# ArduinoRev2.net
KiCad netlist of a schematic drawn in Altium Designer
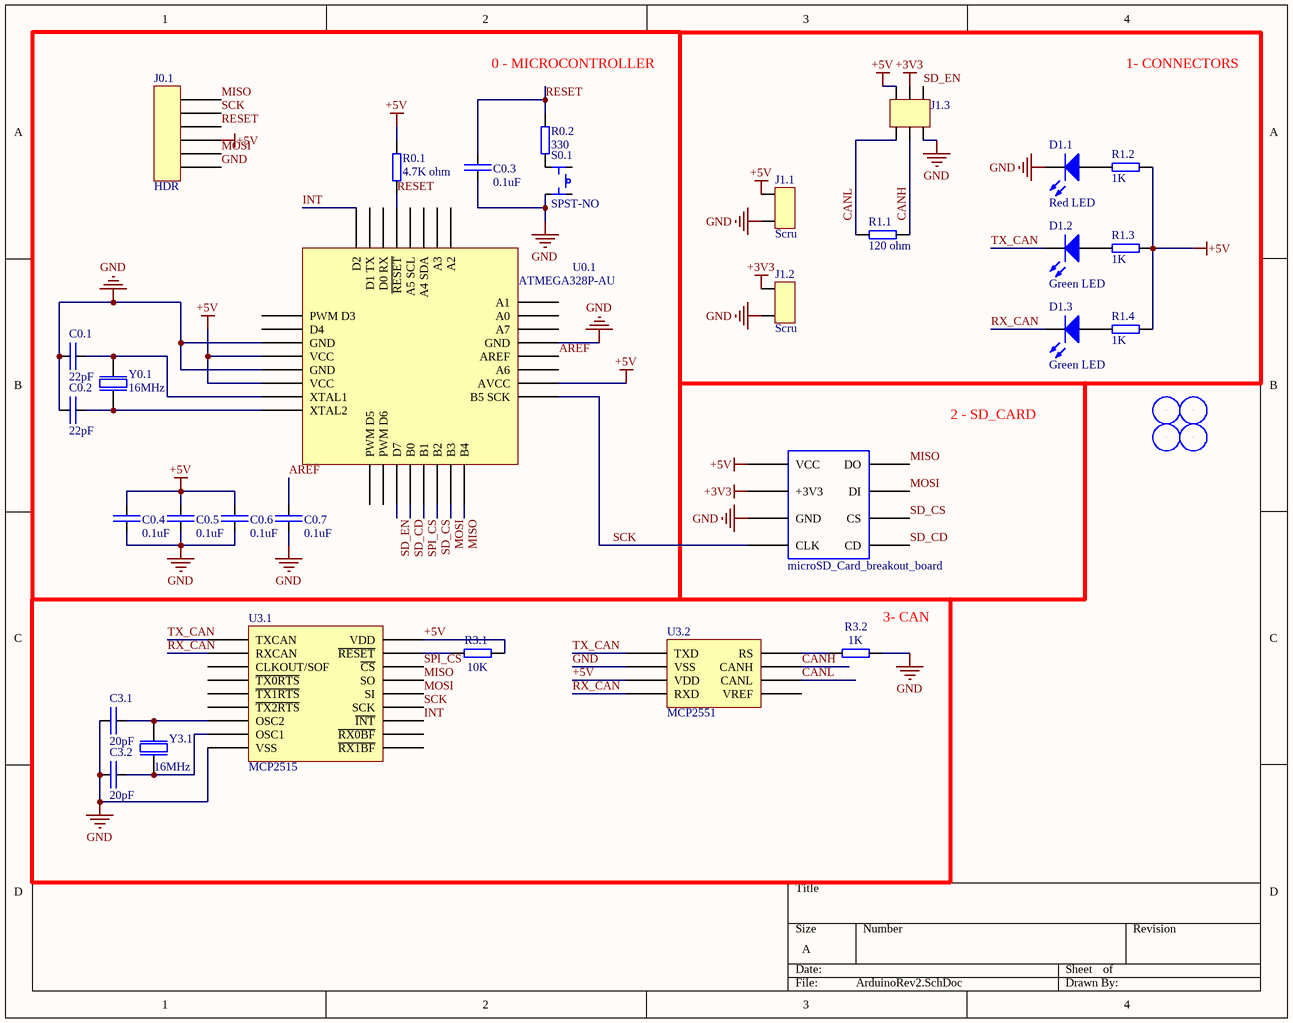
[diagram p0: ArduinoRev2.SchDoc]

(export (version "E")
  (design (tool "Eeschema 10.0.6"))
  (components
    (comp (ref "C0.1")
      (value "22pF")
      (footprint "C0805")
      (description "CAP CER 22PF 50V C0G/NPO 0805")
      (libsource (lib "Atmega328p") (part "CC0805JRNPO9BN220"))
    )
    (comp (ref "C0.2")
      (value "22pF")
      (footprint "C0805")
      (description "CAP CER 22PF 50V C0G/NPO 0805")
      (libsource (lib "Atmega328p") (part "CC0805JRNPO9BN220"))
    )
    (comp (ref "C0.3")
      (value "0.1uF")
      (footprint "C0805")
      (description "CAP CER 0.1UF 50V X7R 0805")
      (fields
        (field (name "MANUFACTURER") "Samsung")
        (field (name "MANUFACTURER PART NUMBER") "CL21B104KBCWPNC")
      )
      (libsource (lib "Capacitors") (part "CL21B104KBCWPNC"))
    )
    (comp (ref "C0.4")
      (value "0.1uF")
      (footprint "C0805")
      (description "CAP CER 0.1UF 50V X7R 0805")
      (fields
        (field (name "MANUFACTURER") "Samsung")
        (field (name "MANUFACTURER PART NUMBER") "CL21B104KBCWPNC")
      )
      (libsource (lib "Capacitors") (part "CL21B104KBCWPNC"))
    )
    (comp (ref "C0.5")
      (value "0.1uF")
      (footprint "C0805")
      (description "CAP CER 0.1UF 50V X7R 0805")
      (fields
        (field (name "MANUFACTURER") "Samsung")
        (field (name "MANUFACTURER PART NUMBER") "CL21B104KBCWPNC")
      )
      (libsource (lib "Capacitors") (part "CL21B104KBCWPNC"))
    )
    (comp (ref "C0.6")
      (value "0.1uF")
      (footprint "C0805")
      (description "CAP CER 0.1UF 50V X7R 0805")
      (fields
        (field (name "MANUFACTURER") "Samsung")
        (field (name "MANUFACTURER PART NUMBER") "CL21B104KBCWPNC")
      )
      (libsource (lib "Capacitors") (part "CL21B104KBCWPNC"))
    )
    (comp (ref "C0.7")
      (value "0.1uF")
      (footprint "C0805")
      (description "CAP CER 0.1UF 50V X7R 0805")
      (fields
        (field (name "MANUFACTURER") "Samsung")
        (field (name "MANUFACTURER PART NUMBER") "CL21B104KBCWPNC")
      )
      (libsource (lib "Capacitors") (part "CL21B104KBCWPNC"))
    )
    (comp (ref "C3.1")
      (value "20pF")
      (footprint "C0805")
      (description "CAP CER 20PF 50V C0G/NP0 0805")
      (fields
        (field (name "MANUFACTURER") "Samsung")
        (field (name "MANUFACTURER PART NUMBER") "CL21B103KBANNNC")
      )
      (libsource (lib "Capacitors") (part "C0805C200J5GACTU"))
    )
    (comp (ref "C3.2")
      (value "20pF")
      (footprint "C0805")
      (description "CAP CER 20PF 50V C0G/NP0 0805")
      (fields
        (field (name "MANUFACTURER") "Samsung")
        (field (name "MANUFACTURER PART NUMBER") "CL21B103KBANNNC")
      )
      (libsource (lib "Capacitors") (part "C0805C200J5GACTU"))
    )
    (comp (ref "D1.1")
      (value "Red LED")
      (footprint "L0805")
      (description "LED RED DIFFUSED 0805 SMD")
      (fields
        (field (name "MANUFACTURER") "Lumex")
        (field (name "MANUFACTURER PART NUMBER") "SML-LXT0805SRW-TR")
      )
      (libsource (lib "Indication & Control") (part "SML-LXT0805SRW-TR"))
    )
    (comp (ref "D1.2")
      (value "Green LED")
      (footprint "L0805")
      (description "LED GREEN DIFFUSED SMD")
      (fields
        (field (name "MANUFACTURER") "Lumex")
        (field (name "MANUFACTURER PART NUMBER") "SML-LXT0805GW-TR")
      )
      (libsource (lib "Indication & Control") (part "SML-LXT0805GW-TR"))
    )
    (comp (ref "D1.3")
      (value "Green LED")
      (footprint "L0805")
      (description "LED GREEN DIFFUSED SMD")
      (fields
        (field (name "MANUFACTURER") "Lumex")
        (field (name "MANUFACTURER PART NUMBER") "SML-LXT0805GW-TR")
      )
      (libsource (lib "Indication & Control") (part "SML-LXT0805GW-TR"))
    )
    (comp (ref "J0.1")
      (value "HDR")
      (footprint "961206-6404-AR")
      (description "CONN HEADER VERT 6POS 2.54MM")
      (libsource (lib "Atmega328p") (part "961206-6404-AR"))
    )
    (comp (ref "J1.1")
      (value "Scru")
      (footprint "5mm 2POS Screw terminal")
      (libsource (lib "Connectors") (part "5mm 2POS Screw terminal"))
    )
    (comp (ref "J1.2")
      (value "Scru")
      (footprint "5mm 2POS Screw terminal")
      (libsource (lib "Connectors") (part "5mm 2POS Screw terminal"))
    )
    (comp (ref "J1.3")
      (value "43045-0600")
      (footprint "Micro-Fit 3.0 6pos")
      (description "Micro-fit 3.0 6pos right-angle")
      (fields (field (name "MANUFACTURER") "Molex") (field (name "MANUFACTURER PART NUMBER") "43045-0612"))
      (libsource (lib "Connectors") (part "43045-0600"))
    )
    (comp (ref "M1")
      (value "3mm Mounting Hole")
      (footprint "3mm Mounting Hole")
      (libsource (lib "Misc Components") (part "3mm Mounting Hole"))
    )
    (comp (ref "M2")
      (value "3mm Mounting Hole")
      (footprint "3mm Mounting Hole")
      (libsource (lib "Misc Components") (part "3mm Mounting Hole"))
    )
    (comp (ref "M3")
      (value "3mm Mounting Hole")
      (footprint "3mm Mounting Hole")
      (libsource (lib "Misc Components") (part "3mm Mounting Hole"))
    )
    (comp (ref "M4")
      (value "3mm Mounting Hole")
      (footprint "3mm Mounting Hole")
      (libsource (lib "Misc Components") (part "3mm Mounting Hole"))
    )
    (comp (ref "R0.1")
      (value "4.7K ohm")
      (footprint "R0805")
      (description "RES SMD 4.7K OHM 5% 1/8W 0805")
      (libsource (lib "Atmega328p") (part "RC0805JR-074K7L"))
    )
    (comp (ref "R0.2")
      (value "330")
      (footprint "R0805")
      (description "RES SMD 330 OHM 5% 1/8W 0805")
      (libsource (lib "Atmega328p") (part "RC0805JR-074K7L_1"))
    )
    (comp (ref "R1.1")
      (value "120 ohm")
      (footprint "R0805")
      (description "RES SMD 120 OHM 1% 1/8W 0805")
      (libsource (lib "Resistors") (part "ERJ6ENV1200V"))
    )
    (comp (ref "R1.2")
      (value "1K")
      (footprint "R0805")
      (description "RES SMD 1K OHM 1% 1/8W 0805")
      (fields
        (field (name "MANUFACTURER") "Panasonic")
        (field (name "MANUFACTURER PART NUMBER") "ERJ6ENF1001V")
      )
      (libsource (lib "Resistors") (part "ERJ6ENF1001V"))
    )
    (comp (ref "R1.3")
      (value "1K")
      (footprint "R0805")
      (description "RES SMD 1K OHM 1% 1/8W 0805")
      (fields
        (field (name "MANUFACTURER") "Panasonic")
        (field (name "MANUFACTURER PART NUMBER") "ERJ6ENF1001V")
      )
      (libsource (lib "Resistors") (part "ERJ6ENF1001V"))
    )
    (comp (ref "R1.4")
      (value "1K")
      (footprint "R0805")
      (description "RES SMD 1K OHM 1% 1/8W 0805")
      (fields
        (field (name "MANUFACTURER") "Panasonic")
        (field (name "MANUFACTURER PART NUMBER") "ERJ6ENF1001V")
      )
      (libsource (lib "Resistors") (part "ERJ6ENF1001V"))
    )
    (comp (ref "R3.1")
      (value "10K")
      (footprint "R0805")
      (description "RES SMD 10K OHM 1% 1/8W 0805")
      (fields (field (name "MANUFACTURER") "Yageo") (field (name "MANUFACTURER PART NUMBER") "ERJ-6ENF1002V"))
      (libsource (lib "Resistors") (part "ERJ6ENF1002V"))
    )
    (comp (ref "R3.2")
      (value "1K")
      (footprint "R0805")
      (description "RES SMD 1K OHM 1% 1/8W 0805")
      (fields
        (field (name "MANUFACTURER") "Panasonic")
        (field (name "MANUFACTURER PART NUMBER") "ERJ6ENF1001V")
      )
      (libsource (lib "Resistors") (part "ERJ6ENF1001V"))
    )
    (comp (ref "S0.1")
      (value "SPST-NO")
      (footprint "PTS526 SM15 SMTR2 LFS")
      (description "TACT 5.2 X 5.2, 1.5 MM H, 160GF, Tactile Switch SPST-NO Top Actuated Surface Mount")
      (fields
        (field (name "MANUFACTURER") "ITT C&K")
        (field (name "MANUFACTURER PART NUMBER") "PTS526SM15SMTR2LFS")
      )
      (libsource (lib "Indication & Control") (part "PTS526SM15SMTR2LFS"))
    )
    (comp (ref "U0.1")
      (value "ATMEGA328P-AU")
      (footprint "TQFP80P900X900X120-32N")
      (fields (field (name "CREATED BY") "Joseph Park"))
      (libsource (lib "Atmega328p") (part "ATMEGA328P-AU"))
    )
    (comp (ref "U2.1")
      (value "microSD_Card_breakout_board")
      (footprint "Adafruit microSD_breakoutboard")
      (libsource (lib "Atmega328p") (part "microSD_Card_breakout_board"))
    )
    (comp (ref "U3.1")
      (value "MCP2515")
      (footprint "SOP18")
      (description "Stand-Alone CAN Controller with SPI Interface")
      (libsource (lib "Atmega328p") (part "MCP2515"))
    )
    (comp (ref "U3.2")
      (value "MCP2551")
      (footprint "SOP8")
      (description "High Speed Can Transceiver")
      (libsource (lib "Atmega328p") (part "MCP2551"))
    )
    (comp (ref "Y0.1")
      (value "16MHz")
      (footprint "ECS-160-20-3X-TR")
      (description "CRYSTAL 16.0000MHZ 20PF SMD")
      (libsource (lib "Atmega328p") (part "ECS-160-20-3X-TR"))
    )
    (comp (ref "Y3.1")
      (value "16MHz")
      (footprint "ECS-160-20-3X-TR")
      (description "CRYSTAL 16.0000MHZ 20PF SMD")
      (libsource (lib "Atmega328p") (part "ECS-160-20-3X-TR"))
    )
  )
  (nets
    (net (code "1") (name "+3V3") (class "Default")
      (node (ref "J1.2") (pin "1") (pinfunction "1_1") (pintype "passive"))
      (node (ref "J1.3") (pin "5") (pinfunction "5_5") (pintype "passive"))
      (node (ref "U2.1") (pin "2") (pinfunction "+3V3_2") (pintype "passive"))
    )
    (net (code "2") (name "+5V") (class "Default")
      (node (ref "C0.4") (pin "2") (pinfunction "2_2") (pintype "passive"))
      (node (ref "C0.5") (pin "2") (pinfunction "2_2") (pintype "passive"))
      (node (ref "C0.6") (pin "2") (pinfunction "2_2") (pintype "passive"))
      (node (ref "J0.1") (pin "4") (pinfunction "4_4") (pintype "passive"))
      (node (ref "J1.1") (pin "1") (pinfunction "1_1") (pintype "passive"))
      (node (ref "J1.3") (pin "6") (pinfunction "6_6") (pintype "passive"))
      (node (ref "R0.1") (pin "2") (pinfunction "2_2") (pintype "passive"))
      (node (ref "R1.2") (pin "2") (pinfunction "2_2") (pintype "passive"))
      (node (ref "R1.3") (pin "2") (pinfunction "2_2") (pintype "passive"))
      (node (ref "R1.4") (pin "2") (pinfunction "2_2") (pintype "passive"))
      (node (ref "R3.1") (pin "2") (pinfunction "2_2") (pintype "passive"))
      (node (ref "U0.1") (pin "18") (pinfunction "AVCC_18") (pintype "passive"))
      (node (ref "U0.1") (pin "4") (pinfunction "VCC_4") (pintype "passive"))
      (node (ref "U0.1") (pin "6") (pinfunction "VCC_6") (pintype "passive"))
      (node (ref "U2.1") (pin "1") (pinfunction "VCC_1") (pintype "passive"))
      (node (ref "U3.1") (pin "18") (pinfunction "VDD_18") (pintype "passive"))
      (node (ref "U3.2") (pin "3") (pinfunction "VDD_3") (pintype "passive"))
    )
    (net (code "3") (name "/AREF") (class "Default")
      (node (ref "C0.7") (pin "2") (pinfunction "2_2") (pintype "passive"))
      (node (ref "U0.1") (pin "20") (pinfunction "AREF_20") (pintype "passive"))
    )
    (net (code "4") (name "/CANH") (class "Default")
      (node (ref "J1.3") (pin "2") (pinfunction "2_2") (pintype "passive"))
      (node (ref "R1.1") (pin "2") (pinfunction "2_2") (pintype "passive"))
      (node (ref "U3.2") (pin "7") (pinfunction "CANH_7") (pintype "passive"))
    )
    (net (code "5") (name "/CANL") (class "Default")
      (node (ref "J1.3") (pin "3") (pinfunction "3_3") (pintype "passive"))
      (node (ref "R1.1") (pin "1") (pinfunction "1_1") (pintype "passive"))
      (node (ref "U3.2") (pin "6") (pinfunction "CANL_6") (pintype "passive"))
    )
    (net (code "6") (name "/INT") (class "Default")
      (node (ref "U0.1") (pin "32") (pinfunction "D2_32") (pintype "passive"))
      (node (ref "U3.1") (pin "12") (pinfunction "~{INT}_12") (pintype "passive"))
    )
    (net (code "7") (name "/MISO") (class "Default")
      (node (ref "J0.1") (pin "1") (pinfunction "1_1") (pintype "passive"))
      (node (ref "U0.1") (pin "16") (pinfunction "B4_16") (pintype "passive"))
      (node (ref "U2.1") (pin "5") (pinfunction "DO_5") (pintype "passive"))
      (node (ref "U3.1") (pin "15") (pinfunction "SO_15") (pintype "passive"))
    )
    (net (code "8") (name "/MOSI") (class "Default")
      (node (ref "J0.1") (pin "5") (pinfunction "5_5") (pintype "passive"))
      (node (ref "U0.1") (pin "15") (pinfunction "B3_15") (pintype "passive"))
      (node (ref "U2.1") (pin "6") (pinfunction "DI_6") (pintype "passive"))
      (node (ref "U3.1") (pin "14") (pinfunction "SI_14") (pintype "passive"))
    )
    (net (code "9") (name "/RESET") (class "Default")
      (node (ref "C0.3") (pin "2") (pinfunction "2_2") (pintype "passive"))
      (node (ref "J0.1") (pin "3") (pinfunction "3_3") (pintype "passive"))
      (node (ref "R0.1") (pin "1") (pinfunction "1_1") (pintype "passive"))
      (node (ref "R0.2") (pin "2") (pinfunction "2_2") (pintype "passive"))
      (node (ref "U0.1") (pin "29") (pinfunction "~{RESET}_29") (pintype "passive"))
    )
    (net (code "10") (name "/RX_CAN") (class "Default")
      (node (ref "D1.3") (pin "2") (pinfunction "K_2") (pintype "passive"))
      (node (ref "U3.1") (pin "2") (pinfunction "RXCAN_2") (pintype "passive"))
      (node (ref "U3.2") (pin "4") (pinfunction "RXD_4") (pintype "passive"))
    )
    (net (code "11") (name "/SCK") (class "Default")
      (node (ref "J0.1") (pin "2") (pinfunction "2_2") (pintype "passive"))
      (node (ref "U0.1") (pin "17") (pinfunction "B5_SCK_17") (pintype "passive"))
      (node (ref "U2.1") (pin "4") (pinfunction "CLK_4") (pintype "passive"))
      (node (ref "U3.1") (pin "13") (pinfunction "SCK_13") (pintype "passive"))
    )
    (net (code "12") (name "/SD_CD") (class "Default")
      (node (ref "U0.1") (pin "12") (pinfunction "B0_12") (pintype "passive"))
      (node (ref "U2.1") (pin "8") (pinfunction "CD_8") (pintype "passive"))
    )
    (net (code "13") (name "/SD_CS") (class "Default")
      (node (ref "U0.1") (pin "14") (pinfunction "B2_14") (pintype "passive"))
      (node (ref "U2.1") (pin "7") (pinfunction "CS_7") (pintype "passive"))
    )
    (net (code "14") (name "/SD_EN") (class "Default")
      (node (ref "J1.3") (pin "4") (pinfunction "4_4") (pintype "passive"))
      (node (ref "U0.1") (pin "11") (pinfunction "D7_11") (pintype "passive"))
    )
    (net (code "15") (name "/SPI_CS") (class "Default")
      (node (ref "U0.1") (pin "13") (pinfunction "B1_13") (pintype "passive"))
      (node (ref "U3.1") (pin "16") (pinfunction "~{CS}_16") (pintype "passive"))
    )
    (net (code "16") (name "/TX_CAN") (class "Default")
      (node (ref "D1.2") (pin "2") (pinfunction "K_2") (pintype "passive"))
      (node (ref "U3.1") (pin "1") (pinfunction "TXCAN_1") (pintype "passive"))
      (node (ref "U3.2") (pin "1") (pinfunction "TXD_1") (pintype "passive"))
    )
    (net (code "17") (name "GND") (class "Default")
      (node (ref "C0.1") (pin "1") (pinfunction "1_1") (pintype "passive"))
      (node (ref "C0.2") (pin "1") (pinfunction "1_1") (pintype "passive"))
      (node (ref "C0.3") (pin "1") (pinfunction "1_1") (pintype "passive"))
      (node (ref "C0.4") (pin "1") (pinfunction "1_1") (pintype "passive"))
      (node (ref "C0.5") (pin "1") (pinfunction "1_1") (pintype "passive"))
      (node (ref "C0.6") (pin "1") (pinfunction "1_1") (pintype "passive"))
      (node (ref "C0.7") (pin "1") (pinfunction "1_1") (pintype "passive"))
      (node (ref "C3.1") (pin "1") (pinfunction "1_1") (pintype "passive"))
      (node (ref "C3.2") (pin "1") (pinfunction "1_1") (pintype "passive"))
      (node (ref "D1.1") (pin "2") (pinfunction "K_2") (pintype "passive"))
      (node (ref "J0.1") (pin "6") (pinfunction "6_6") (pintype "passive"))
      (node (ref "J1.1") (pin "2") (pinfunction "2_2") (pintype "passive"))
      (node (ref "J1.2") (pin "2") (pinfunction "2_2") (pintype "passive"))
      (node (ref "J1.3") (pin "1") (pinfunction "1_1") (pintype "passive"))
      (node (ref "R3.2") (pin "2") (pinfunction "2_2") (pintype "passive"))
      (node (ref "S0.1") (pin "3") (pinfunction "NO_3") (pintype "passive"))
      (node (ref "U0.1") (pin "21") (pinfunction "GND_21") (pintype "passive"))
      (node (ref "U0.1") (pin "3") (pinfunction "GND_3") (pintype "passive"))
      (node (ref "U0.1") (pin "5") (pinfunction "GND_5") (pintype "passive"))
      (node (ref "U2.1") (pin "3") (pinfunction "GND_3") (pintype "passive"))
      (node (ref "U3.1") (pin "9") (pinfunction "VSS_9") (pintype "passive"))
      (node (ref "U3.2") (pin "2") (pinfunction "VSS_2") (pintype "passive"))
    )
    (net (code "18") (name "Net-(D1.1-A)") (class "Default")
      (node (ref "D1.1") (pin "1") (pinfunction "A_1") (pintype "passive"))
      (node (ref "R1.2") (pin "1") (pinfunction "1_1") (pintype "passive"))
    )
    (net (code "19") (name "Net-(D1.2-A)") (class "Default")
      (node (ref "D1.2") (pin "1") (pinfunction "A_1") (pintype "passive"))
      (node (ref "R1.3") (pin "1") (pinfunction "1_1") (pintype "passive"))
    )
    (net (code "20") (name "Net-(D1.3-A)") (class "Default")
      (node (ref "D1.3") (pin "1") (pinfunction "A_1") (pintype "passive"))
      (node (ref "R1.4") (pin "1") (pinfunction "1_1") (pintype "passive"))
    )
    (net (code "21") (name "Net-(R0.2-Pad1)") (class "Default")
      (node (ref "R0.2") (pin "1") (pinfunction "1_1") (pintype "passive"))
      (node (ref "S0.1") (pin "1") (pinfunction "COM_1") (pintype "passive"))
    )
    (net (code "22") (name "Net-(U0.1-XTAL1)") (class "Default")
      (node (ref "C0.1") (pin "2") (pinfunction "2_2") (pintype "passive"))
      (node (ref "U0.1") (pin "7") (pinfunction "XTAL1_7") (pintype "passive"))
      (node (ref "Y0.1") (pin "2") (pinfunction "2_2") (pintype "passive"))
    )
    (net (code "23") (name "Net-(U0.1-XTAL2)") (class "Default")
      (node (ref "C0.2") (pin "2") (pinfunction "2_2") (pintype "passive"))
      (node (ref "U0.1") (pin "8") (pinfunction "XTAL2_8") (pintype "passive"))
      (node (ref "Y0.1") (pin "1") (pinfunction "1_1") (pintype "passive"))
    )
    (net (code "24") (name "Net-(U3.1-OSC1)") (class "Default")
      (node (ref "C3.2") (pin "2") (pinfunction "2_2") (pintype "passive"))
      (node (ref "U3.1") (pin "8") (pinfunction "OSC1_8") (pintype "passive"))
      (node (ref "Y3.1") (pin "1") (pinfunction "1_1") (pintype "passive"))
    )
    (net (code "25") (name "Net-(U3.1-OSC2)") (class "Default")
      (node (ref "C3.1") (pin "2") (pinfunction "2_2") (pintype "passive"))
      (node (ref "U3.1") (pin "7") (pinfunction "OSC2_7") (pintype "passive"))
      (node (ref "Y3.1") (pin "2") (pinfunction "2_2") (pintype "passive"))
    )
    (net (code "26") (name "Net-(U3.1-~{RESET})") (class "Default")
      (node (ref "R3.1") (pin "1") (pinfunction "1_1") (pintype "passive"))
      (node (ref "U3.1") (pin "17") (pinfunction "~{RESET}_17") (pintype "passive"))
    )
    (net (code "27") (name "Net-(U3.2-RS)") (class "Default")
      (node (ref "R3.2") (pin "1") (pinfunction "1_1") (pintype "passive"))
      (node (ref "U3.2") (pin "8") (pinfunction "RS_8") (pintype "passive"))
    )
    (net (code "28") (name "unconnected-(M1-Pad1)") (class "Default")
      (node (ref "M1") (pin "1") (pinfunction "1_1") (pintype "passive"))
    )
    (net (code "29") (name "unconnected-(M2-Pad1)") (class "Default")
      (node (ref "M2") (pin "1") (pinfunction "1_1") (pintype "passive"))
    )
    (net (code "30") (name "unconnected-(M3-Pad1)") (class "Default")
      (node (ref "M3") (pin "1") (pinfunction "1_1") (pintype "passive"))
    )
    (net (code "31") (name "unconnected-(M4-Pad1)") (class "Default")
      (node (ref "M4") (pin "1") (pinfunction "1_1") (pintype "passive"))
    )
    (net (code "32") (name "unconnected-(S0.1-COM-Pad2)") (class "Default")
      (node (ref "S0.1") (pin "2") (pinfunction "COM_2") (pintype "passive"))
    )
    (net (code "33") (name "unconnected-(S0.1-NO-Pad4)") (class "Default")
      (node (ref "S0.1") (pin "4") (pinfunction "NO_4") (pintype "passive"))
    )
    (net (code "34") (name "unconnected-(U0.1-A0-Pad23)") (class "Default")
      (node (ref "U0.1") (pin "23") (pinfunction "A0_23") (pintype "passive"))
    )
    (net (code "35") (name "unconnected-(U0.1-A1-Pad24)") (class "Default")
      (node (ref "U0.1") (pin "24") (pinfunction "A1_24") (pintype "passive"))
    )
    (net (code "36") (name "unconnected-(U0.1-A2-Pad25)") (class "Default")
      (node (ref "U0.1") (pin "25") (pinfunction "A2_25") (pintype "passive"))
    )
    (net (code "37") (name "unconnected-(U0.1-A3-Pad26)") (class "Default")
      (node (ref "U0.1") (pin "26") (pinfunction "A3_26") (pintype "passive"))
    )
    (net (code "38") (name "unconnected-(U0.1-A4_SDA-Pad27)") (class "Default")
      (node (ref "U0.1") (pin "27") (pinfunction "A4_SDA_27") (pintype "passive"))
    )
    (net (code "39") (name "unconnected-(U0.1-A5_SCL-Pad28)") (class "Default")
      (node (ref "U0.1") (pin "28") (pinfunction "A5_SCL_28") (pintype "passive"))
    )
    (net (code "40") (name "unconnected-(U0.1-A6-Pad19)") (class "Default")
      (node (ref "U0.1") (pin "19") (pinfunction "A6_19") (pintype "passive"))
    )
    (net (code "41") (name "unconnected-(U0.1-A7-Pad22)") (class "Default")
      (node (ref "U0.1") (pin "22") (pinfunction "A7_22") (pintype "passive"))
    )
    (net (code "42") (name "unconnected-(U0.1-D0_RX-Pad30)") (class "Default")
      (node (ref "U0.1") (pin "30") (pinfunction "D0_RX_30") (pintype "passive"))
    )
    (net (code "43") (name "unconnected-(U0.1-D1_TX-Pad31)") (class "Default")
      (node (ref "U0.1") (pin "31") (pinfunction "D1_TX_31") (pintype "passive"))
    )
    (net (code "44") (name "unconnected-(U0.1-D4-Pad2)") (class "Default")
      (node (ref "U0.1") (pin "2") (pinfunction "D4_2") (pintype "passive"))
    )
    (net (code "45") (name "unconnected-(U0.1-PWM_D3-Pad1)") (class "Default")
      (node (ref "U0.1") (pin "1") (pinfunction "PWM_D3_1") (pintype "passive"))
    )
    (net (code "46") (name "unconnected-(U0.1-PWM_D5-Pad9)") (class "Default")
      (node (ref "U0.1") (pin "9") (pinfunction "PWM_D5_9") (pintype "passive"))
    )
    (net (code "47") (name "unconnected-(U0.1-PWM_D6-Pad10)") (class "Default")
      (node (ref "U0.1") (pin "10") (pinfunction "PWM_D6_10") (pintype "passive"))
    )
    (net (code "48") (name "unconnected-(U3.1-CLKOUT{slash}SOF-Pad3)") (class "Default")
      (node (ref "U3.1") (pin "3") (pinfunction "CLKOUT/SOF_3") (pintype "passive"))
    )
    (net (code "49") (name "unconnected-(U3.1-~{RX0BF}-Pad11)") (class "Default")
      (node (ref "U3.1") (pin "11") (pinfunction "~{RX0BF}_11") (pintype "passive"))
    )
    (net (code "50") (name "unconnected-(U3.1-~{RX1BF}-Pad10)") (class "Default")
      (node (ref "U3.1") (pin "10") (pinfunction "~{RX1BF}_10") (pintype "passive"))
    )
    (net (code "51") (name "unconnected-(U3.1-~{TX0RTS}-Pad4)") (class "Default")
      (node (ref "U3.1") (pin "4") (pinfunction "~{TX0RTS}_4") (pintype "passive"))
    )
    (net (code "52") (name "unconnected-(U3.1-~{TX1RTS}-Pad5)") (class "Default")
      (node (ref "U3.1") (pin "5") (pinfunction "~{TX1RTS}_5") (pintype "passive"))
    )
    (net (code "53") (name "unconnected-(U3.1-~{TX2RTS}-Pad6)") (class "Default")
      (node (ref "U3.1") (pin "6") (pinfunction "~{TX2RTS}_6") (pintype "passive"))
    )
    (net (code "54") (name "unconnected-(U3.2-VREF-Pad5)") (class "Default")
      (node (ref "U3.2") (pin "5") (pinfunction "VREF_5") (pintype "passive"))
    )
  )
)
